# DC075B_LMK_CLOCK_CIRCUIT.net
KiCad netlist of a schematic drawn in Altium Designer
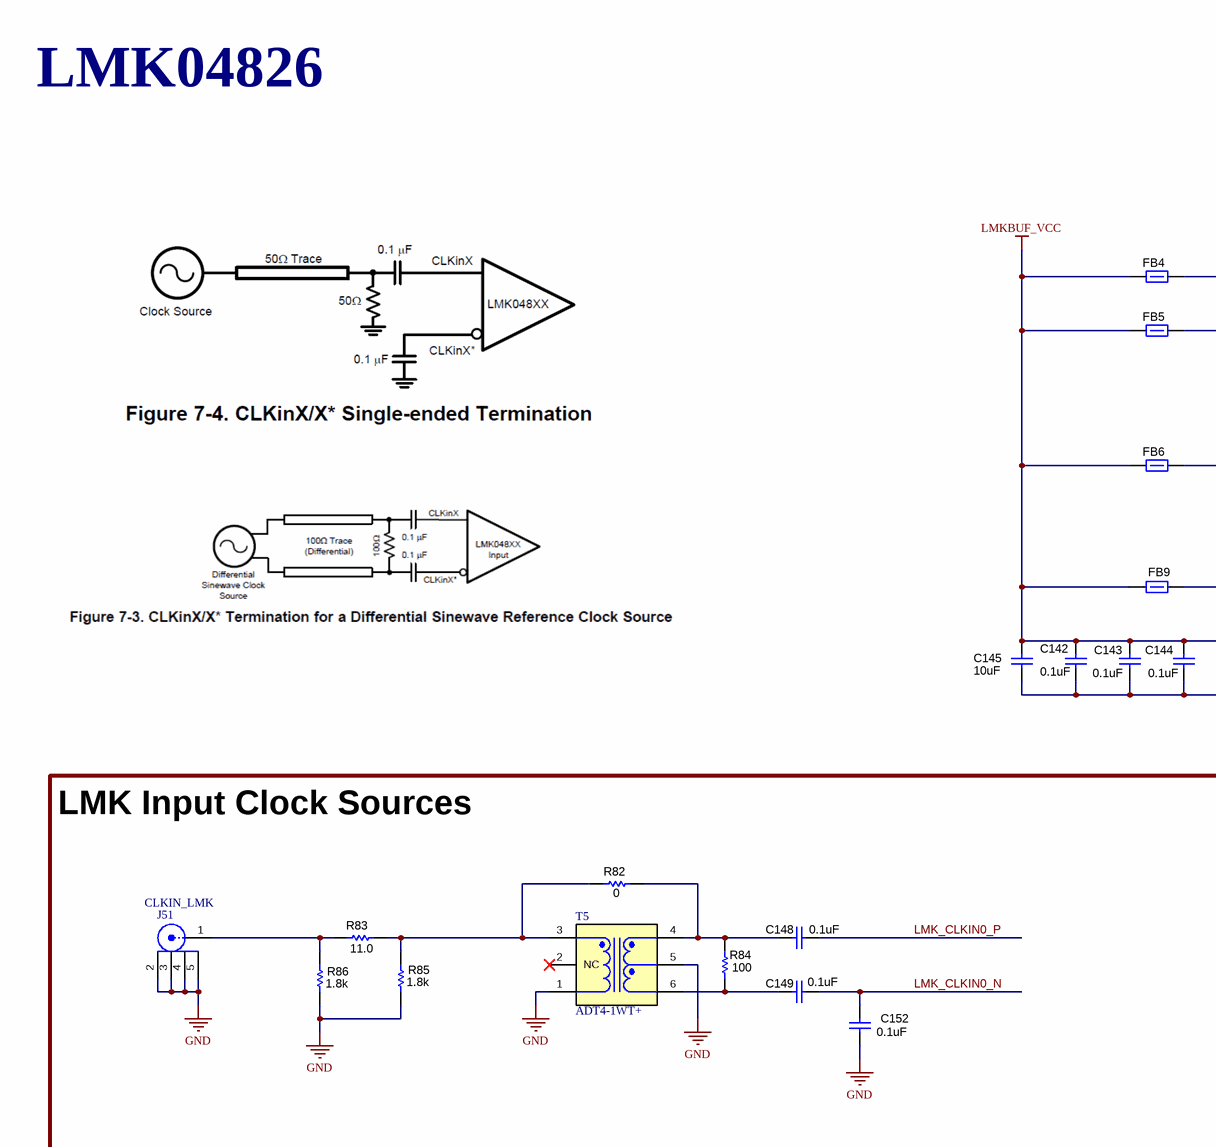
[diagram p0: DC075B_LMK_CLOCK_CIRCUIT.SchDoc, top left]
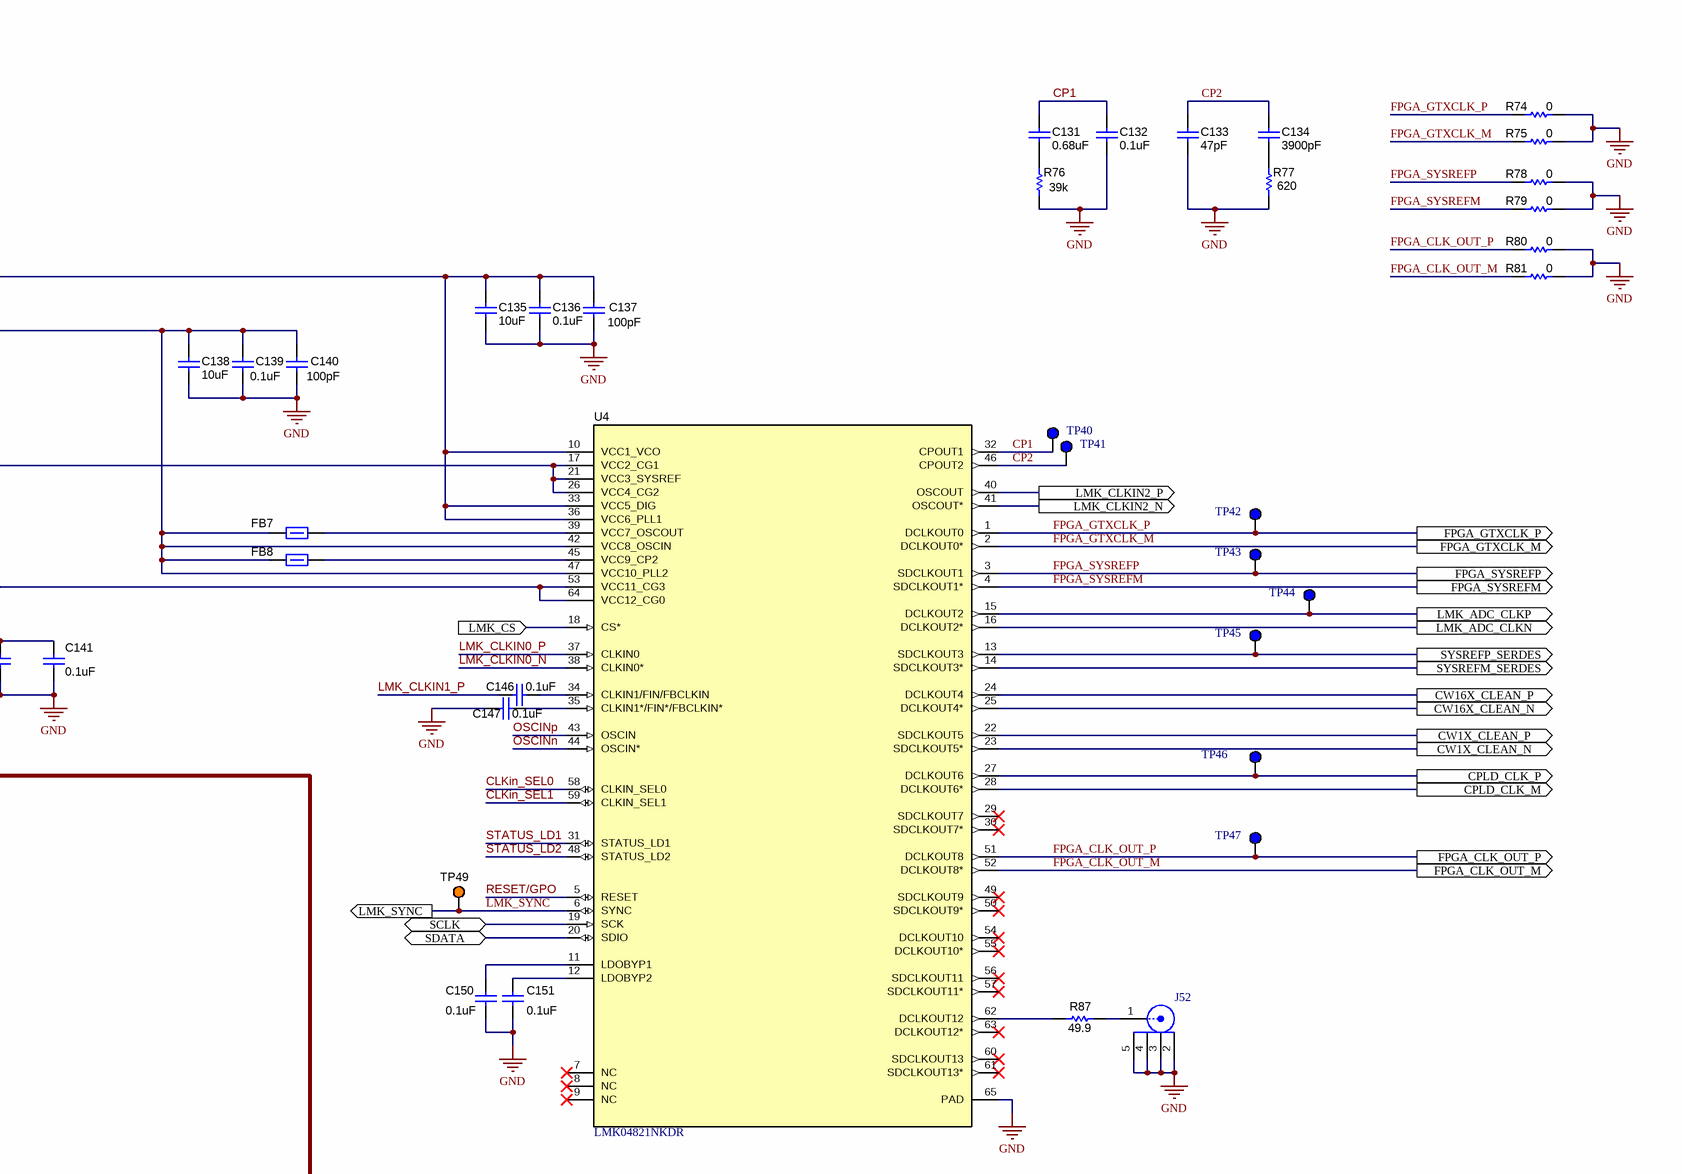
[diagram p1: DC075B_LMK_CLOCK_CIRCUIT.SchDoc, top right]
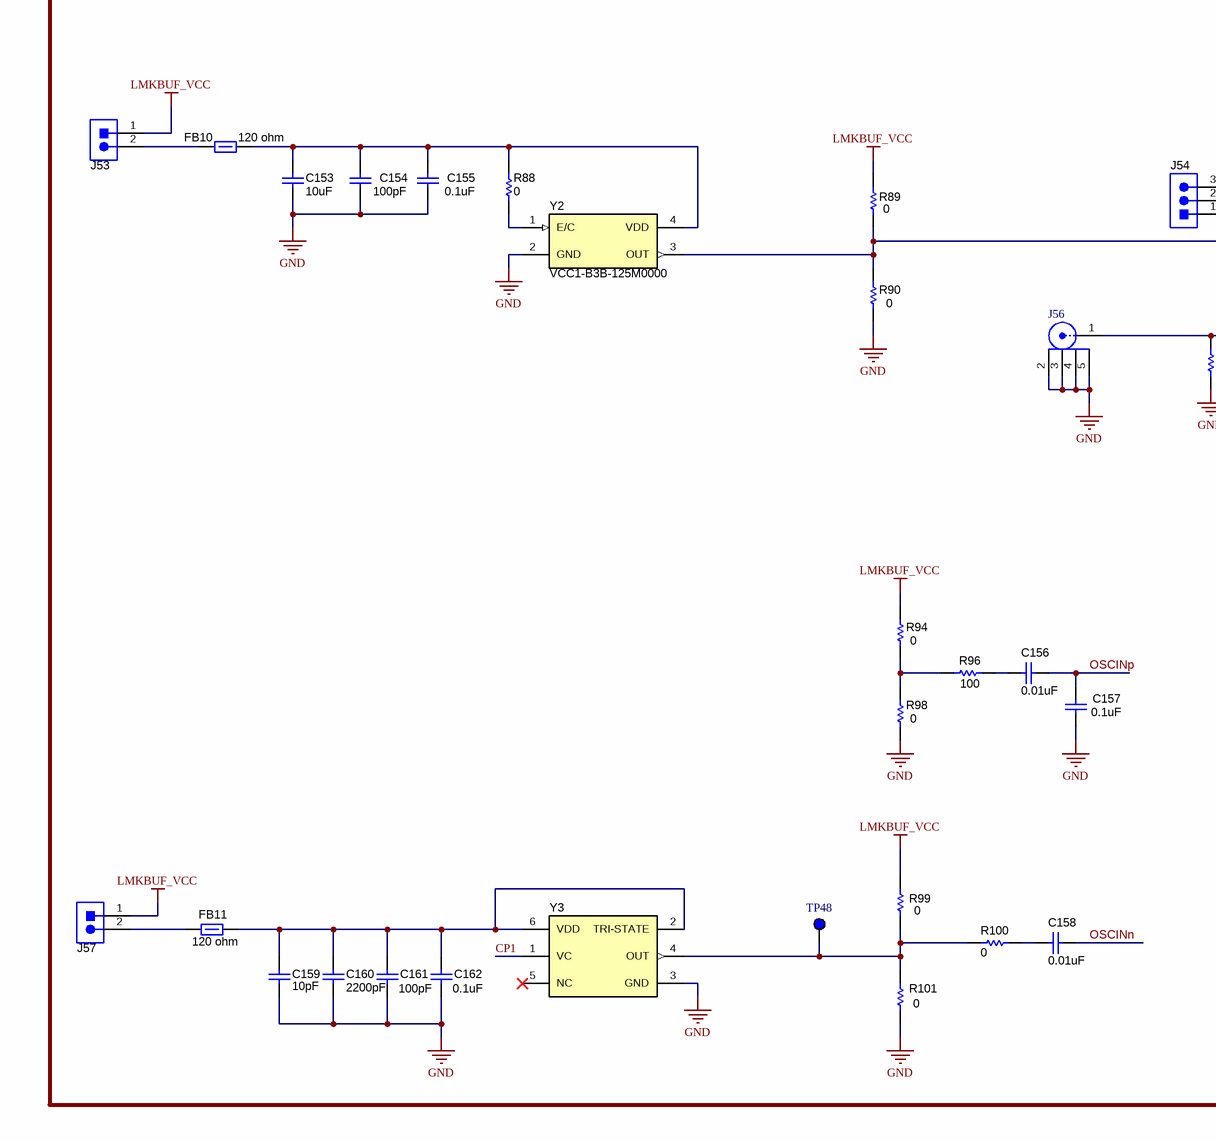
[diagram p2: DC075B_LMK_CLOCK_CIRCUIT.SchDoc, bottom left]
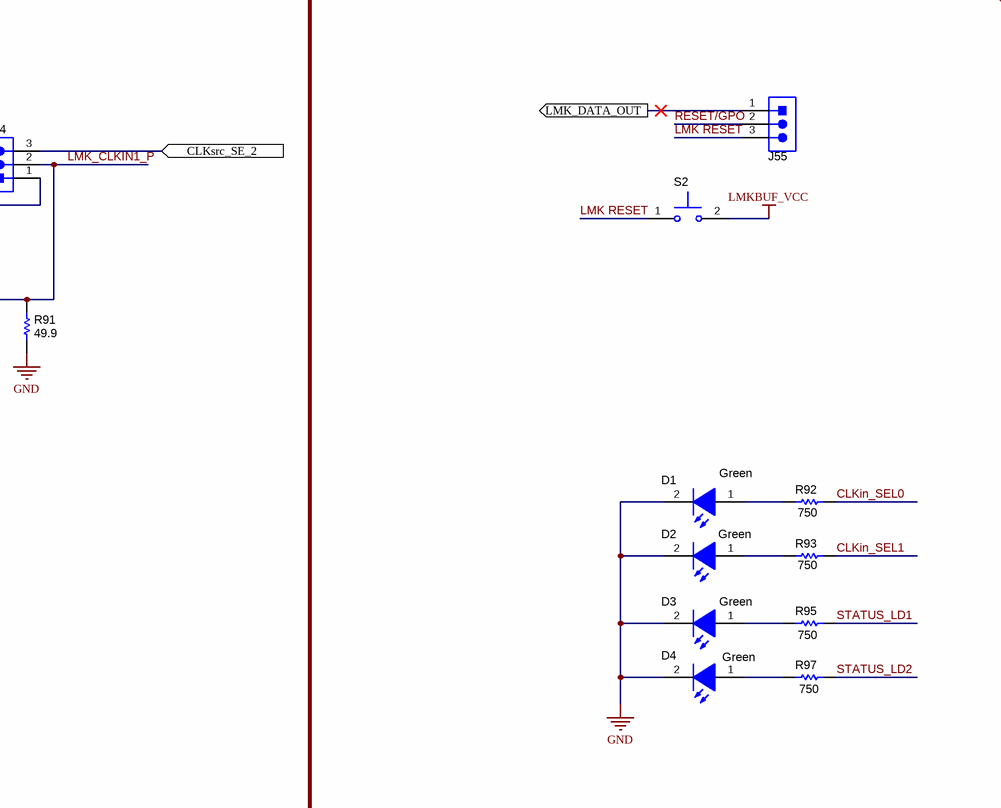
[diagram p3: DC075B_LMK_CLOCK_CIRCUIT.SchDoc, bottom right]

(export (version "E")
  (design (tool "Eeschema 10.0.6"))
  (components
    (comp (ref "C131")
      (value "0.68uF")
      (footprint "0603_HV")
      (description "CAP, CERM, 0.68 uF, 10 V, +/- 10%, X5R, 0603")
      (fields
        (field (name "PARTNUMBER") "C0603C684K8PACTU")
        (field (name "MANUFACTURER") "Kemet")
        (field (name "PUBLISHER") "Texas Instruments")
      )
      (libsource (lib "Altium Vault - TI") (part "Capacitor"))
    )
    (comp (ref "C132")
      (value "0.1uF")
      (footprint "0402")
      (description "CAP, CERM, 0.1 uF, 16 V, +/- 10%, X7R, 0402")
      (fields
        (field (name "PARTNUMBER") "GRM155R71C104KA88D")
        (field (name "MANUFACTURER") "MuRata")
        (field (name "PUBLISHER") "Texas Instruments")
      )
      (libsource (lib "Altium Vault - TI") (part "Capacitor"))
    )
    (comp (ref "C133")
      (value "C0603C470J1GACAUTO")
      (footprint "0603")
      (description "CAP, CERM, 47 pF, 100 V,+/- 5%, C0G/NP0, AEC-Q200 Grade 1, 0603")
      (fields (field (name "VALUEDISPLAYED") "47pF") (field (name "MANUFACTURER") "Kemet"))
      (libsource (lib "Altium Vault - TI") (part "CMP-0085572-1"))
    )
    (comp (ref "C134")
      (value "3900pF")
      (footprint "0402")
      (description "CAP, CERM, 3900 pF, 50 V,+/- 10%, X7R, 0402")
      (fields
        (field (name "PARTNUMBER") "CL05B392KB5NNNC")
        (field (name "MANUFACTURER") "Samsung Electro-Mechanics")
      )
      (libsource (lib "Altium Vault - TI") (part "CMP-0085576-2"))
    )
    (comp (ref "C135")
      (value "10uF")
      (footprint "0603_HV")
      (description "CAP, CERM, 10 uF, 6.3 V, +/- 20%, X5R, 0603")
      (fields
        (field (name "PARTNUMBER") "GRM188R60J106ME47D")
        (field (name "MANUFACTURER") "MuRata")
        (field (name "PUBLISHER") "Texas Instruments")
      )
      (libsource (lib "Altium Vault - TI") (part "Capacitor"))
    )
    (comp (ref "C136")
      (value "0.1uF")
      (footprint "0402")
      (description "CAP, CERM, 0.1 uF, 16 V, +/- 10%, X7R, 0402")
      (fields
        (field (name "PARTNUMBER") "GRM155R71C104KA88D")
        (field (name "MANUFACTURER") "MuRata")
        (field (name "PUBLISHER") "Texas Instruments")
      )
      (libsource (lib "Altium Vault - TI") (part "Capacitor"))
    )
    (comp (ref "C137")
      (value "100pF")
      (footprint "0402")
      (description "CAP, CERM, 100 pF, 50 V, +/- 10%, X7R, 0402")
      (fields
        (field (name "PARTNUMBER") "CC0402KRX7R9BB101")
        (field (name "MANUFACTURER") "Yageo America")
        (field (name "PUBLISHER") "Texas Instruments")
      )
      (libsource (lib "Altium Vault - TI") (part "Capacitor"))
    )
    (comp (ref "C138")
      (value "10uF")
      (footprint "0603_HV")
      (description "CAP, CERM, 10 uF, 6.3 V, +/- 20%, X5R, 0603")
      (fields
        (field (name "PARTNUMBER") "GRM188R60J106ME47D")
        (field (name "MANUFACTURER") "MuRata")
        (field (name "PUBLISHER") "Texas Instruments")
      )
      (libsource (lib "Altium Vault - TI") (part "Capacitor"))
    )
    (comp (ref "C139")
      (value "0.1uF")
      (footprint "0402")
      (description "CAP, CERM, 0.1 uF, 16 V, +/- 10%, X7R, 0402")
      (fields
        (field (name "PARTNUMBER") "GRM155R71C104KA88D")
        (field (name "MANUFACTURER") "MuRata")
        (field (name "PUBLISHER") "Texas Instruments")
      )
      (libsource (lib "Altium Vault - TI") (part "Capacitor"))
    )
    (comp (ref "C140")
      (value "100pF")
      (footprint "0402")
      (description "CAP, CERM, 100 pF, 50 V, +/- 10%, X7R, 0402")
      (fields
        (field (name "PARTNUMBER") "CC0402KRX7R9BB101")
        (field (name "MANUFACTURER") "Yageo America")
        (field (name "PUBLISHER") "Texas Instruments")
      )
      (libsource (lib "Altium Vault - TI") (part "Capacitor"))
    )
    (comp (ref "C141")
      (value "0.1uF")
      (footprint "0402")
      (description "CAP, CERM, 0.1 uF, 16 V, +/- 10%, X7R, 0402")
      (fields
        (field (name "PARTNUMBER") "GRM155R71C104KA88D")
        (field (name "MANUFACTURER") "MuRata")
        (field (name "PUBLISHER") "Texas Instruments")
      )
      (libsource (lib "Altium Vault - TI") (part "Capacitor"))
    )
    (comp (ref "C142")
      (value "0.1uF")
      (footprint "0402")
      (description "CAP, CERM, 0.1 uF, 16 V, +/- 10%, X7R, 0402")
      (fields
        (field (name "PARTNUMBER") "GRM155R71C104KA88D")
        (field (name "MANUFACTURER") "MuRata")
        (field (name "PUBLISHER") "Texas Instruments")
      )
      (libsource (lib "Altium Vault - TI") (part "Capacitor"))
    )
    (comp (ref "C143")
      (value "0.1uF")
      (footprint "0402")
      (description "CAP, CERM, 0.1 uF, 16 V, +/- 10%, X7R, 0402")
      (fields
        (field (name "PARTNUMBER") "GRM155R71C104KA88D")
        (field (name "MANUFACTURER") "MuRata")
        (field (name "PUBLISHER") "Texas Instruments")
      )
      (libsource (lib "Altium Vault - TI") (part "Capacitor"))
    )
    (comp (ref "C144")
      (value "0.1uF")
      (footprint "0402")
      (description "CAP, CERM, 0.1 uF, 16 V, +/- 10%, X7R, 0402")
      (fields
        (field (name "PARTNUMBER") "GRM155R71C104KA88D")
        (field (name "MANUFACTURER") "MuRata")
        (field (name "PUBLISHER") "Texas Instruments")
      )
      (libsource (lib "Altium Vault - TI") (part "Capacitor"))
    )
    (comp (ref "C145")
      (value "10uF")
      (footprint "0603_HV")
      (description "CAP, CERM, 10 uF, 6.3 V, +/- 20%, X5R, 0603")
      (fields
        (field (name "PARTNUMBER") "GRM188R60J106ME47D")
        (field (name "MANUFACTURER") "MuRata")
        (field (name "PUBLISHER") "Texas Instruments")
      )
      (libsource (lib "Altium Vault - TI") (part "Capacitor"))
    )
    (comp (ref "C146")
      (value "0.1uF")
      (footprint "0402")
      (description "CAP, CERM, 0.1 uF, 16 V, +/- 10%, X7R, 0402")
      (fields
        (field (name "PARTNUMBER") "GRM155R71C104KA88D")
        (field (name "MANUFACTURER") "MuRata")
        (field (name "PUBLISHER") "Texas Instruments")
      )
      (libsource (lib "Altium Vault - TI") (part "Capacitor"))
    )
    (comp (ref "C147")
      (value "0.1uF")
      (footprint "0402")
      (description "CAP, CERM, 0.1 uF, 16 V, +/- 10%, X7R, 0402")
      (fields
        (field (name "PARTNUMBER") "GRM155R71C104KA88D")
        (field (name "MANUFACTURER") "MuRata")
        (field (name "PUBLISHER") "Texas Instruments")
      )
      (libsource (lib "Altium Vault - TI") (part "Capacitor"))
    )
    (comp (ref "C148")
      (value "0.1uF")
      (footprint "0402")
      (description "CAP, CERM, 0.1 uF, 16 V, +/- 10%, X7R, 0402")
      (fields
        (field (name "PARTNUMBER") "GRM155R71C104KA88D")
        (field (name "MANUFACTURER") "MuRata")
        (field (name "PUBLISHER") "Texas Instruments")
      )
      (libsource (lib "Altium Vault - TI") (part "Capacitor"))
    )
    (comp (ref "C149")
      (value "0.1uF")
      (footprint "0402")
      (description "CAP, CERM, 0.1 uF, 16 V, +/- 10%, X7R, 0402")
      (fields
        (field (name "PARTNUMBER") "GRM155R71C104KA88D")
        (field (name "MANUFACTURER") "MuRata")
        (field (name "PUBLISHER") "Texas Instruments")
      )
      (libsource (lib "Altium Vault - TI") (part "Capacitor"))
    )
    (comp (ref "C150")
      (value "0.1uF")
      (footprint "0402")
      (description "CAP, CERM, 0.1 uF, 16 V, +/- 10%, X7R, 0402")
      (fields
        (field (name "PARTNUMBER") "GRM155R71C104KA88D")
        (field (name "MANUFACTURER") "MuRata")
        (field (name "PUBLISHER") "Texas Instruments")
      )
      (libsource (lib "Altium Vault - TI") (part "Capacitor"))
    )
    (comp (ref "C151")
      (value "0.1uF")
      (footprint "0402")
      (description "CAP, CERM, 0.1 uF, 16 V, +/- 10%, X7R, 0402")
      (fields
        (field (name "PARTNUMBER") "GRM155R71C104KA88D")
        (field (name "MANUFACTURER") "MuRata")
        (field (name "PUBLISHER") "Texas Instruments")
      )
      (libsource (lib "Altium Vault - TI") (part "Capacitor"))
    )
    (comp (ref "C152")
      (value "0.1uF")
      (footprint "0603_HV")
      (description "CAP, CERM, 0.1 uF, 25 V, +/- 5%, X7R, 0603")
      (fields
        (field (name "PARTNUMBER") "06033C104JAT2A")
        (field (name "MANUFACTURER") "AVX")
        (field (name "PUBLISHER") "Texas Instruments")
      )
      (libsource (lib "Altium Vault - TI") (part "Capacitor"))
    )
    (comp (ref "C153")
      (value "10uF")
      (footprint "0603_HV")
      (description "CAP, CERM, 10 uF, 6.3 V, +/- 20%, X5R, 0603")
      (fields
        (field (name "PARTNUMBER") "GRM188R60J106ME47D")
        (field (name "MANUFACTURER") "MuRata")
        (field (name "PUBLISHER") "Texas Instruments")
      )
      (libsource (lib "Altium Vault - TI") (part "Capacitor"))
    )
    (comp (ref "C154")
      (value "100pF")
      (footprint "0402")
      (description "CAP, CERM, 100 pF, 50 V, +/- 10%, X7R, 0402")
      (fields
        (field (name "PARTNUMBER") "CC0402KRX7R9BB101")
        (field (name "MANUFACTURER") "Yageo America")
        (field (name "PUBLISHER") "Texas Instruments")
      )
      (libsource (lib "Altium Vault - TI") (part "Capacitor"))
    )
    (comp (ref "C155")
      (value "0.1uF")
      (footprint "0402")
      (description "CAP, CERM, 0.1 uF, 16 V, +/- 10%, X7R, 0402")
      (fields
        (field (name "PARTNUMBER") "GRM155R71C104KA88D")
        (field (name "MANUFACTURER") "MuRata")
        (field (name "PUBLISHER") "Texas Instruments")
      )
      (libsource (lib "Altium Vault - TI") (part "Capacitor"))
    )
    (comp (ref "C156")
      (value "GRM155R61C103KA01D")
      (footprint "0402")
      (description "CAP, CERM, 0.01 uF, 16 V, +/- 10%, X5R, 0402")
      (fields
        (field (name "VALUEDISPLAYED") "0.01uF")
        (field (name "MANUFACTURER") "MuRata")
        (field (name "PUBLISHER") "Texas Instruments")
      )
      (libsource (lib "Altium Vault - TI") (part "Capacitor"))
    )
    (comp (ref "C157")
      (value "0.1uF")
      (footprint "0402")
      (description "CAP, CERM, 0.1 uF, 16 V, +/- 10%, X7R, 0402")
      (fields
        (field (name "PARTNUMBER") "GRM155R71C104KA88D")
        (field (name "MANUFACTURER") "MuRata")
        (field (name "PUBLISHER") "Texas Instruments")
      )
      (libsource (lib "Altium Vault - TI") (part "Capacitor"))
    )
    (comp (ref "C158")
      (value "GRM155R61C103KA01D")
      (footprint "0402")
      (description "CAP, CERM, 0.01 uF, 16 V, +/- 10%, X5R, 0402")
      (fields
        (field (name "VALUEDISPLAYED") "0.01uF")
        (field (name "MANUFACTURER") "MuRata")
        (field (name "PUBLISHER") "Texas Instruments")
      )
      (libsource (lib "Altium Vault - TI") (part "Capacitor"))
    )
    (comp (ref "C159")
      (value "C0402C100C8GACTU")
      (footprint "0402")
      (description "CAP, CERM, 10 pF, 10 V,+/- 2.5%, C0G/NP0, 0402")
      (fields
        (field (name "MANUFACTURER") "Kemet")
        (field (name "VALUEDISPLAYED") "10pF")
        (field (name "PUBLISHER") "Texas Instruments")
      )
      (libsource (lib "Altium Vault - TI") (part "CMP-0064914-2"))
    )
    (comp (ref "C160")
      (value "500R07W222KV4T")
      (footprint "0402_065")
      (description "CAP, CERM, 2200 pF, 50 V,+/- 10%, X7R, 0402")
      (fields (field (name "VALUEDISPLAYED") "2200pF") (field (name "MANUFACTURER") "Johanson Technology"))
      (libsource (lib "Altium Vault - TI") (part "Capacitor"))
    )
    (comp (ref "C161")
      (value "100pF")
      (footprint "0402")
      (description "CAP, CERM, 100 pF, 50 V, +/- 10%, X7R, 0402")
      (fields
        (field (name "PARTNUMBER") "CC0402KRX7R9BB101")
        (field (name "MANUFACTURER") "Yageo America")
        (field (name "PUBLISHER") "Texas Instruments")
      )
      (libsource (lib "Altium Vault - TI") (part "Capacitor"))
    )
    (comp (ref "C162")
      (value "0.1uF")
      (footprint "0402")
      (description "CAP, CERM, 0.1 uF, 16 V, +/- 10%, X7R, 0402")
      (fields
        (field (name "PARTNUMBER") "GRM155R71C104KA88D")
        (field (name "MANUFACTURER") "MuRata")
        (field (name "PUBLISHER") "Texas Instruments")
      )
      (libsource (lib "Altium Vault - TI") (part "Capacitor"))
    )
    (comp (ref "D1")
      (value "Green")
      (footprint "LED_LTST-C190_G")
      (description "LED, Green, SMD")
      (fields (field (name "MANUFACTURER") "Lite-On") (field (name "PARTNUMBER") "LTST-C190KGKT"))
      (libsource (lib "Altium Vault - TI") (part "CMP-0002840-2"))
    )
    (comp (ref "D2")
      (value "Green")
      (footprint "LED_LTST-C190_G")
      (description "LED, Green, SMD")
      (fields (field (name "MANUFACTURER") "Lite-On") (field (name "PARTNUMBER") "LTST-C190KGKT"))
      (libsource (lib "Altium Vault - TI") (part "CMP-0002840-2"))
    )
    (comp (ref "D3")
      (value "Green")
      (footprint "LED_LTST-C190_G")
      (description "LED, Green, SMD")
      (fields (field (name "MANUFACTURER") "Lite-On") (field (name "PARTNUMBER") "LTST-C190KGKT"))
      (libsource (lib "Altium Vault - TI") (part "CMP-0002840-2"))
    )
    (comp (ref "D4")
      (value "Green")
      (footprint "LED_LTST-C190_G")
      (description "LED, Green, SMD")
      (fields (field (name "MANUFACTURER") "Lite-On") (field (name "PARTNUMBER") "LTST-C190KGKT"))
      (libsource (lib "Altium Vault - TI") (part "CMP-0002840-2"))
    )
    (comp (ref "FB4")
      (value "BLM21AG121SN1D")
      (footprint "0805")
      (description "Ferrite Bead, 120 ohm @ 100 MHz, 0.8 A, 0805")
      (fields (field (name "MANUFACTURER") "MuRata") (field (name "PUBLISHER") "Texas Instruments"))
      (libsource (lib "Altium Vault - TI") (part "Ferrite_Bead"))
    )
    (comp (ref "FB5")
      (value "BLM21AG121SN1D")
      (footprint "0805")
      (description "Ferrite Bead, 120 ohm @ 100 MHz, 0.8 A, 0805")
      (fields (field (name "MANUFACTURER") "MuRata") (field (name "PUBLISHER") "Texas Instruments"))
      (libsource (lib "Altium Vault - TI") (part "Ferrite_Bead"))
    )
    (comp (ref "FB6")
      (value "BLM21AG121SN1D")
      (footprint "0805")
      (description "Ferrite Bead, 120 ohm @ 100 MHz, 0.8 A, 0805")
      (fields (field (name "MANUFACTURER") "MuRata") (field (name "PUBLISHER") "Texas Instruments"))
      (libsource (lib "Altium Vault - TI") (part "Ferrite_Bead"))
    )
    (comp (ref "FB7")
      (value "BLM21AG121SN1D")
      (footprint "0805")
      (description "Ferrite Bead, 120 ohm @ 100 MHz, 0.8 A, 0805")
      (fields (field (name "MANUFACTURER") "MuRata") (field (name "PUBLISHER") "Texas Instruments"))
      (libsource (lib "Altium Vault - TI") (part "Ferrite_Bead"))
    )
    (comp (ref "FB8")
      (value "BLM21AG121SN1D")
      (footprint "0805")
      (description "Ferrite Bead, 120 ohm @ 100 MHz, 0.8 A, 0805")
      (fields (field (name "MANUFACTURER") "MuRata") (field (name "PUBLISHER") "Texas Instruments"))
      (libsource (lib "Altium Vault - TI") (part "Ferrite_Bead"))
    )
    (comp (ref "FB9")
      (value "BLM21AG121SN1D")
      (footprint "0805")
      (description "Ferrite Bead, 120 ohm @ 100 MHz, 0.8 A, 0805")
      (fields (field (name "MANUFACTURER") "MuRata") (field (name "PUBLISHER") "Texas Instruments"))
      (libsource (lib "Altium Vault - TI") (part "Ferrite_Bead"))
    )
    (comp (ref "FB10")
      (value "120 ohm")
      (footprint "1206")
      (description "Ferrite Bead, 120 ohm @ 100 MHz, 4 A, 1206")
      (fields
        (field (name "MANUFACTURER") "Laird-Signal Integrity Products")
        (field (name "PARTNUMBER") "HI1206P121R-10")
        (field (name "PUBLISHER") "Texas Instruments")
      )
      (libsource (lib "Altium Vault - TI") (part "Ferrite_Bead"))
    )
    (comp (ref "FB11")
      (value "120 ohm")
      (footprint "1206")
      (description "Ferrite Bead, 120 ohm @ 100 MHz, 4 A, 1206")
      (fields
        (field (name "MANUFACTURER") "Laird-Signal Integrity Products")
        (field (name "PARTNUMBER") "HI1206P121R-10")
        (field (name "PUBLISHER") "Texas Instruments")
      )
      (libsource (lib "Altium Vault - TI") (part "Ferrite_Bead"))
    )
    (comp (ref "J51")
      (value "5-1814832-1")
      (footprint "TE_5-1814832-1")
      (description "SMA Straight PCB Socket Die Cast, 50 Ohm, TH")
      (fields (field (name "MANUFACTURER") "TE Connectivity") (field (name "PUBLISHER") "Texas Instruments"))
      (libsource (lib "Altium Vault - TI") (part "SMA_Contact1_GND2345"))
    )
    (comp (ref "J52")
      (value "5-1814832-1")
      (footprint "TE_5-1814832-1")
      (description "SMA Straight PCB Socket Die Cast, 50 Ohm, TH")
      (fields (field (name "MANUFACTURER") "TE Connectivity") (field (name "PUBLISHER") "Texas Instruments"))
      (libsource (lib "Altium Vault - TI") (part "SMA_Contact1_GND2345"))
    )
    (comp (ref "J53")
      (value "TSW-102-07-G-S")
      (footprint "TSW-102-07-G-S")
      (description "Header, 100mil, 2x1, Gold, TH")
      (fields (field (name "MANUFACTURER") "Samtec"))
      (libsource (lib "Altium Vault - TI") (part "Header_2x1"))
    )
    (comp (ref "J54")
      (value "TSW-103-07-G-S")
      (footprint "TSW-103-07-G-S")
      (description "Header, 100mil, 3x1, Gold, TH")
      (fields (field (name "MANUFACTURER") "Samtec"))
      (libsource (lib "Altium Vault - TI") (part "Header_3x1"))
    )
    (comp (ref "J55")
      (value "TSW-103-07-G-S")
      (footprint "TSW-103-07-G-S")
      (description "Header, 100mil, 3x1, Gold, TH")
      (fields (field (name "MANUFACTURER") "Samtec"))
      (libsource (lib "") (part "Header_3x1_1"))
    )
    (comp (ref "J56")
      (value "5-1814832-1")
      (footprint "TE_5-1814832-1")
      (description "SMA Straight PCB Socket Die Cast, 50 Ohm, TH")
      (fields (field (name "MANUFACTURER") "TE Connectivity") (field (name "PUBLISHER") "Texas Instruments"))
      (libsource (lib "Altium Vault - TI") (part "SMA_Contact1_GND2345"))
    )
    (comp (ref "J57")
      (value "TSW-102-07-G-S")
      (footprint "TSW-102-07-G-S")
      (description "Header, 100mil, 2x1, Gold, TH")
      (fields (field (name "MANUFACTURER") "Samtec"))
      (libsource (lib "Altium Vault - TI") (part "Header_2x1"))
    )
    (comp (ref "R74")
      (value "0")
      (footprint "0402")
      (description "RES, 0, 5%, 0.063 W, AEC-Q200 Grade 0, 0402")
      (fields (field (name "MANUFACTURER") "Vishay-Dale") (field (name "PARTNUMBER") "CRCW04020000Z0ED"))
      (libsource (lib "Altium Vault - TI") (part "Resistor"))
    )
    (comp (ref "R75")
      (value "0")
      (footprint "0402")
      (description "RES, 0, 5%, 0.063 W, AEC-Q200 Grade 0, 0402")
      (fields (field (name "MANUFACTURER") "Vishay-Dale") (field (name "PARTNUMBER") "CRCW04020000Z0ED"))
      (libsource (lib "Altium Vault - TI") (part "Resistor"))
    )
    (comp (ref "R76")
      (value "39k")
      (footprint "0402")
      (description "RES, 39 k, 5%, 0.063 W, AEC-Q200 Grade 0, 0402")
      (fields (field (name "MANUFACTURER") "Vishay-Dale") (field (name "PARTNUMBER") "CRCW040239K0JNED"))
      (libsource (lib "Altium Vault - TI") (part "Resistor"))
    )
    (comp (ref "R77")
      (value "620")
      (footprint "0402")
      (description "RES, 620, 5%, 0.063 W, AEC-Q200 Grade 0, 0402")
      (fields (field (name "MANUFACTURER") "Vishay-Dale") (field (name "PARTNUMBER") "CRCW0402620RJNED"))
      (libsource (lib "Altium Vault - TI") (part "Resistor"))
    )
    (comp (ref "R78")
      (value "0")
      (footprint "0402")
      (description "RES, 0, 5%, 0.063 W, AEC-Q200 Grade 0, 0402")
      (fields (field (name "MANUFACTURER") "Vishay-Dale") (field (name "PARTNUMBER") "CRCW04020000Z0ED"))
      (libsource (lib "Altium Vault - TI") (part "Resistor"))
    )
    (comp (ref "R79")
      (value "0")
      (footprint "0402")
      (description "RES, 0, 5%, 0.063 W, AEC-Q200 Grade 0, 0402")
      (fields (field (name "MANUFACTURER") "Vishay-Dale") (field (name "PARTNUMBER") "CRCW04020000Z0ED"))
      (libsource (lib "Altium Vault - TI") (part "Resistor"))
    )
    (comp (ref "R80")
      (value "0")
      (footprint "0402")
      (description "RES, 0, 5%, 0.063 W, AEC-Q200 Grade 0, 0402")
      (fields (field (name "MANUFACTURER") "Vishay-Dale") (field (name "PARTNUMBER") "CRCW04020000Z0ED"))
      (libsource (lib "Altium Vault - TI") (part "Resistor"))
    )
    (comp (ref "R81")
      (value "0")
      (footprint "0402")
      (description "RES, 0, 5%, 0.063 W, AEC-Q200 Grade 0, 0402")
      (fields (field (name "MANUFACTURER") "Vishay-Dale") (field (name "PARTNUMBER") "CRCW04020000Z0ED"))
      (libsource (lib "Altium Vault - TI") (part "Resistor"))
    )
    (comp (ref "R82")
      (value "0")
      (footprint "0402")
      (description "RES, 0, 5%, 0.063 W, AEC-Q200 Grade 0, 0402")
      (fields (field (name "MANUFACTURER") "Vishay-Dale") (field (name "PARTNUMBER") "CRCW04020000Z0ED"))
      (libsource (lib "Altium Vault - TI") (part "Resistor"))
    )
    (comp (ref "R83")
      (value "11.0")
      (footprint "0402")
      (description "RES, 11.0, 1%, 0.063 W, AEC-Q200 Grade 0, 0402")
      (fields (field (name "MANUFACTURER") "Vishay-Dale") (field (name "PARTNUMBER") "CRCW040211R0FKED"))
      (libsource (lib "Altium Vault - TI") (part "Resistor"))
    )
    (comp (ref "R84")
      (value "ERJ-2RKF1000X")
      (footprint "0402")
      (description "RES, 100, 1%, 0.1 W, 0402")
      (fields
        (field (name "MANUFACTURER") "Panasonic")
        (field (name "VALUEDISPLAYED") "100")
        (field (name "PUBLISHER") "Texas Instruments")
      )
      (libsource (lib "Altium Vault - TI") (part "Resistor"))
    )
    (comp (ref "R85")
      (value "1.8k")
      (footprint "0402")
      (description "RES, 1.8 k, 5%, 0.063 W, AEC-Q200 Grade 0, 0402")
      (fields (field (name "MANUFACTURER") "Vishay-Dale") (field (name "PARTNUMBER") "CRCW04021K80JNED"))
      (libsource (lib "Altium Vault - TI") (part "Resistor"))
    )
    (comp (ref "R86")
      (value "1.8k")
      (footprint "0402")
      (description "RES, 1.8 k, 5%, 0.063 W, AEC-Q200 Grade 0, 0402")
      (fields (field (name "MANUFACTURER") "Vishay-Dale") (field (name "PARTNUMBER") "CRCW04021K80JNED"))
      (libsource (lib "Altium Vault - TI") (part "Resistor"))
    )
    (comp (ref "R87")
      (value "49.9")
      (footprint "0402")
      (description "RES, 49.9, 1%, 0.063 W, AEC-Q200 Grade 0, 0402")
      (fields (field (name "MANUFACTURER") "Vishay-Dale") (field (name "PARTNUMBER") "CRCW040249R9FKED"))
      (libsource (lib "Altium Vault - TI") (part "Resistor"))
    )
    (comp (ref "R88")
      (value "CRCW04020000Z0ED")
      (footprint "0402")
      (description "RES, 0, 5%, 0.063 W, AEC-Q200 Grade 0, 0402")
      (fields (field (name "VALUEDISPLAYED") "0") (field (name "MANUFACTURER") "Vishay-Dale"))
      (libsource (lib "Altium Vault - TI") (part "Resistor"))
    )
    (comp (ref "R89")
      (value "0")
      (footprint "0402")
      (description "RES, 0, 5%, 0.063 W, AEC-Q200 Grade 0, 0402")
      (fields (field (name "MANUFACTURER") "Vishay-Dale") (field (name "PARTNUMBER") "CRCW04020000Z0ED"))
      (libsource (lib "Altium Vault - TI") (part "Resistor"))
    )
    (comp (ref "R90")
      (value "0")
      (footprint "0402")
      (description "RES, 0, 5%, 0.063 W, AEC-Q200 Grade 0, 0402")
      (fields (field (name "MANUFACTURER") "Vishay-Dale") (field (name "PARTNUMBER") "CRCW04020000Z0ED"))
      (libsource (lib "Altium Vault - TI") (part "Resistor"))
    )
    (comp (ref "R91")
      (value "49.9")
      (footprint "0402")
      (description "RES, 49.9, 1%, 0.063 W, AEC-Q200 Grade 0, 0402")
      (fields (field (name "MANUFACTURER") "Vishay-Dale") (field (name "PARTNUMBER") "CRCW040249R9FKED"))
      (libsource (lib "Altium Vault - TI") (part "Resistor"))
    )
    (comp (ref "R92")
      (value "750")
      (footprint "0402")
      (description "RES, 750, 5%, 0.063 W, AEC-Q200 Grade 0, 0402")
      (fields (field (name "MANUFACTURER") "Vishay-Dale") (field (name "PARTNUMBER") "CRCW0402750RJNED"))
      (libsource (lib "Altium Vault - TI") (part "Resistor"))
    )
    (comp (ref "R93")
      (value "750")
      (footprint "0402")
      (description "RES, 750, 5%, 0.063 W, AEC-Q200 Grade 0, 0402")
      (fields (field (name "MANUFACTURER") "Vishay-Dale") (field (name "PARTNUMBER") "CRCW0402750RJNED"))
      (libsource (lib "Altium Vault - TI") (part "Resistor"))
    )
    (comp (ref "R94")
      (value "0")
      (footprint "0402")
      (description "RES, 0, 5%, 0.063 W, AEC-Q200 Grade 0, 0402")
      (fields (field (name "MANUFACTURER") "Vishay-Dale") (field (name "PARTNUMBER") "CRCW04020000Z0ED"))
      (libsource (lib "Altium Vault - TI") (part "Resistor"))
    )
    (comp (ref "R95")
      (value "750")
      (footprint "0402")
      (description "RES, 750, 5%, 0.063 W, AEC-Q200 Grade 0, 0402")
      (fields (field (name "MANUFACTURER") "Vishay-Dale") (field (name "PARTNUMBER") "CRCW0402750RJNED"))
      (libsource (lib "Altium Vault - TI") (part "Resistor"))
    )
    (comp (ref "R96")
      (value "ERJ-2RKF1000X")
      (footprint "0402")
      (description "RES, 100, 1%, 0.1 W, 0402")
      (fields
        (field (name "MANUFACTURER") "Panasonic")
        (field (name "VALUEDISPLAYED") "100")
        (field (name "PUBLISHER") "Texas Instruments")
      )
      (libsource (lib "Altium Vault - TI") (part "Resistor"))
    )
    (comp (ref "R97")
      (value "750")
      (footprint "0402")
      (description "RES, 750, 5%, 0.063 W, AEC-Q200 Grade 0, 0402")
      (fields (field (name "MANUFACTURER") "Vishay-Dale") (field (name "PARTNUMBER") "CRCW0402750RJNED"))
      (libsource (lib "Altium Vault - TI") (part "Resistor"))
    )
    (comp (ref "R98")
      (value "0")
      (footprint "0402")
      (description "RES, 0, 5%, 0.063 W, AEC-Q200 Grade 0, 0402")
      (fields (field (name "MANUFACTURER") "Vishay-Dale") (field (name "PARTNUMBER") "CRCW04020000Z0ED"))
      (libsource (lib "Altium Vault - TI") (part "Resistor"))
    )
    (comp (ref "R99")
      (value "0")
      (footprint "0402")
      (description "RES, 0, 5%, 0.063 W, AEC-Q200 Grade 0, 0402")
      (fields (field (name "MANUFACTURER") "Vishay-Dale") (field (name "PARTNUMBER") "CRCW04020000Z0ED"))
      (libsource (lib "Altium Vault - TI") (part "Resistor"))
    )
    (comp (ref "R100")
      (value "CRCW04020000Z0ED")
      (footprint "0402")
      (description "RES, 0, 5%, 0.063 W, AEC-Q200 Grade 0, 0402")
      (fields (field (name "MANUFACTURER") "Vishay-Dale") (field (name "VALUEDISPLAYED") "0"))
      (libsource (lib "Altium Vault - TI") (part "Resistor"))
    )
    (comp (ref "R101")
      (value "0")
      (footprint "0402")
      (description "RES, 0, 5%, 0.063 W, AEC-Q200 Grade 0, 0402")
      (fields (field (name "MANUFACTURER") "Vishay-Dale") (field (name "PARTNUMBER") "CRCW04020000Z0ED"))
      (libsource (lib "Altium Vault - TI") (part "Resistor"))
    )
    (comp (ref "S2")
      (value "SKRKAEE020")
      (footprint "SW_SKRKAE")
      (description "Switch, SPST-NO, 0.05 A, 12 VDC, SMT")
      (fields (field (name "MANUFACTURER") "Alps") (field (name "PUBLISHER") "Texas Instruments"))
      (libsource (lib "Altium Vault - TI") (part "Switch_PushButton"))
    )
    (comp (ref "T5")
      (value "ADT4-1WT+")
      (footprint "MNC_CD542")
      (description "RF Transformer, 50 ohm, 2 to 775 MHz, SMT")
      (fields (field (name "MANUFACTURER") "Minicircuits") (field (name "PUBLISHER") "Texas Instruments"))
      (libsource (lib "Altium Vault - TI") (part "MNC_ADT4-1WT+"))
    )
    (comp (ref "TP40")
      (value "5117")
      (footprint "Keystone5117")
      (description "Test Point, Miniature, Blue, TH")
      (fields (field (name "MANUFACTURER") "Keystone") (field (name "PUBLISHER") "Texas Instruments"))
      (libsource (lib "Altium Vault - TI") (part "5117"))
    )
    (comp (ref "TP41")
      (value "5117")
      (footprint "Keystone5117")
      (description "Test Point, Miniature, Blue, TH")
      (fields (field (name "MANUFACTURER") "Keystone") (field (name "PUBLISHER") "Texas Instruments"))
      (libsource (lib "Altium Vault - TI") (part "5117"))
    )
    (comp (ref "TP42")
      (value "5117")
      (footprint "Keystone5117")
      (description "Test Point, Miniature, Blue, TH")
      (fields (field (name "MANUFACTURER") "Keystone") (field (name "PUBLISHER") "Texas Instruments"))
      (libsource (lib "Altium Vault - TI") (part "5117"))
    )
    (comp (ref "TP43")
      (value "5117")
      (footprint "Keystone5117")
      (description "Test Point, Miniature, Blue, TH")
      (fields (field (name "MANUFACTURER") "Keystone") (field (name "PUBLISHER") "Texas Instruments"))
      (libsource (lib "Altium Vault - TI") (part "5117"))
    )
    (comp (ref "TP44")
      (value "5117")
      (footprint "Keystone5117")
      (description "Test Point, Miniature, Blue, TH")
      (fields (field (name "MANUFACTURER") "Keystone") (field (name "PUBLISHER") "Texas Instruments"))
      (libsource (lib "Altium Vault - TI") (part "5117"))
    )
    (comp (ref "TP45")
      (value "5117")
      (footprint "Keystone5117")
      (description "Test Point, Miniature, Blue, TH")
      (fields (field (name "MANUFACTURER") "Keystone") (field (name "PUBLISHER") "Texas Instruments"))
      (libsource (lib "Altium Vault - TI") (part "5117"))
    )
    (comp (ref "TP46")
      (value "5117")
      (footprint "Keystone5117")
      (description "Test Point, Miniature, Blue, TH")
      (fields (field (name "MANUFACTURER") "Keystone") (field (name "PUBLISHER") "Texas Instruments"))
      (libsource (lib "Altium Vault - TI") (part "5117"))
    )
    (comp (ref "TP47")
      (value "5117")
      (footprint "Keystone5117")
      (description "Test Point, Miniature, Blue, TH")
      (fields (field (name "MANUFACTURER") "Keystone") (field (name "PUBLISHER") "Texas Instruments"))
      (libsource (lib "Altium Vault - TI") (part "5117"))
    )
    (comp (ref "TP48")
      (value "5117")
      (footprint "Keystone5117")
      (description "Test Point, Miniature, Blue, TH")
      (fields (field (name "MANUFACTURER") "Keystone") (field (name "PUBLISHER") "Texas Instruments"))
      (libsource (lib "Altium Vault - TI") (part "5117"))
    )
    (comp (ref "TP49")
      (value "5003")
      (footprint "Keystone5003")
      (description "Test Point, Miniature, Orange, TH")
      (fields (field (name "MANUFACTURER") "Keystone") (field (name "PUBLISHER") "Texas Instruments"))
      (libsource (lib "Altium Vault - TI") (part "5003"))
    )
    (comp (ref "U4")
      (value "LMK04821NKDR")
      (footprint "NKD0064A")
      (description "Ultra Low Jitter Synthesizer and Jitter Cleaner with JESD204B Support, NKD0064A (WQFN-64)")
      (fields
        (field (name "ALTERNATE PARTNUMBER") "LMK04821NKDT")
        (field (name "MANUFACTURER") "Texas Instruments")
      )
      (libsource (lib "Altium Vault - TI") (part "LMK0482x"))
    )
    (comp (ref "Y2")
      (value "VCC1-B3B-125M0000")
      (footprint "Vectron_VCC1")
      (description "OSC, 3.3 V, 125 MHz, 15 pF, SMD")
      (fields (field (name "MANUFACTURER") "Microsemi"))
      (libsource (lib "Altium Vault - TI") (part "OSC_4P_EC"))
    )
    (comp (ref "Y3")
      (value "ASVV-40.000MHZ-N102-T")
      (footprint "ABRACON_ASVV")
      (description "OSC, 40 MHz, 3.3V, SMD")
      (fields (field (name "MANUFACTURER") "Abracon Corporation"))
      (libsource (lib "Altium Vault - TI") (part "OSC_ASVV"))
    )
  )
  (nets
    (net (code "1") (name "/CLKin_SEL0") (class "Default")
      (node (ref "R92") (pin "2") (pinfunction "2_2") (pintype "passive"))
      (node (ref "U4") (pin "58") (pinfunction "CLKIN_SEL0_58") (pintype "bidirectional"))
    )
    (net (code "2") (name "/CLKin_SEL1") (class "Default")
      (node (ref "R93") (pin "2") (pinfunction "2_2") (pintype "passive"))
      (node (ref "U4") (pin "59") (pinfunction "CLKIN_SEL1_59") (pintype "bidirectional"))
    )
    (net (code "3") (name "/CLKsrc_SE_2") (class "Default")
      (node (ref "J54") (pin "3") (pinfunction "3_3") (pintype "passive"))
    )
    (net (code "4") (name "/CP1") (class "Default")
      (node (ref "C131") (pin "2") (pinfunction "2_2") (pintype "passive"))
      (node (ref "C132") (pin "2") (pinfunction "2_2") (pintype "passive"))
      (node (ref "TP40") (pin "1") (pintype "passive"))
      (node (ref "U4") (pin "32") (pinfunction "CPOUT1_32") (pintype "output"))
      (node (ref "Y3") (pin "1") (pinfunction "VC_1") (pintype "power_in"))
    )
    (net (code "5") (name "/CP2") (class "Default")
      (node (ref "C133") (pin "2") (pinfunction "2_2") (pintype "passive"))
      (node (ref "C134") (pin "2") (pinfunction "2_2") (pintype "passive"))
      (node (ref "TP41") (pin "1") (pintype "passive"))
      (node (ref "U4") (pin "46") (pinfunction "CPOUT2_46") (pintype "output"))
    )
    (net (code "6") (name "/CPLD_CLK_M") (class "Default")
      (node (ref "U4") (pin "28") (pinfunction "DCLKOUT6*_28") (pintype "output"))
    )
    (net (code "7") (name "/CPLD_CLK_P") (class "Default")
      (node (ref "TP46") (pin "1") (pintype "passive"))
      (node (ref "U4") (pin "27") (pinfunction "DCLKOUT6_27") (pintype "output"))
    )
    (net (code "8") (name "/CW1X_CLEAN_N") (class "Default")
      (node (ref "U4") (pin "23") (pinfunction "SDCLKOUT5*_23") (pintype "output"))
    )
    (net (code "9") (name "/CW1X_CLEAN_P") (class "Default")
      (node (ref "U4") (pin "22") (pinfunction "SDCLKOUT5_22") (pintype "output"))
    )
    (net (code "10") (name "/CW16X_CLEAN_N") (class "Default")
      (node (ref "U4") (pin "25") (pinfunction "DCLKOUT4*_25") (pintype "output"))
    )
    (net (code "11") (name "/CW16X_CLEAN_P") (class "Default")
      (node (ref "U4") (pin "24") (pinfunction "DCLKOUT4_24") (pintype "output"))
    )
    (net (code "12") (name "/FPGA_CLK_OUT_M") (class "Default")
      (node (ref "R81") (pin "2") (pinfunction "2_2") (pintype "passive"))
      (node (ref "U4") (pin "52") (pinfunction "DCLKOUT8*_52") (pintype "output"))
    )
    (net (code "13") (name "/FPGA_CLK_OUT_P") (class "Default")
      (node (ref "R80") (pin "1") (pinfunction "1_1") (pintype "passive"))
      (node (ref "TP47") (pin "1") (pintype "passive"))
      (node (ref "U4") (pin "51") (pinfunction "DCLKOUT8_51") (pintype "output"))
    )
    (net (code "14") (name "/FPGA_GTXCLK_M") (class "Default")
      (node (ref "R75") (pin "2") (pinfunction "2_2") (pintype "passive"))
      (node (ref "U4") (pin "2") (pinfunction "DCLKOUT0*_2") (pintype "output"))
    )
    (net (code "15") (name "/FPGA_GTXCLK_P") (class "Default")
      (node (ref "R74") (pin "1") (pinfunction "1_1") (pintype "passive"))
      (node (ref "TP42") (pin "1") (pintype "passive"))
      (node (ref "U4") (pin "1") (pinfunction "DCLKOUT0_1") (pintype "output"))
    )
    (net (code "16") (name "/FPGA_SYSREFM") (class "Default")
      (node (ref "R79") (pin "2") (pinfunction "2_2") (pintype "passive"))
      (node (ref "U4") (pin "4") (pinfunction "SDCLKOUT1*_4") (pintype "output"))
    )
    (net (code "17") (name "/FPGA_SYSREFP") (class "Default")
      (node (ref "R78") (pin "1") (pinfunction "1_1") (pintype "passive"))
      (node (ref "TP43") (pin "1") (pintype "passive"))
      (node (ref "U4") (pin "3") (pinfunction "SDCLKOUT1_3") (pintype "output"))
    )
    (net (code "18") (name "/LMK RESET") (class "Default")
      (node (ref "J55") (pin "3") (pinfunction "3_3") (pintype "passive"))
      (node (ref "S2") (pin "1") (pinfunction "1_1") (pintype "passive"))
    )
    (net (code "19") (name "/LMK_ADC_CLKN") (class "Default")
      (node (ref "U4") (pin "16") (pinfunction "DCLKOUT2*_16") (pintype "output"))
    )
    (net (code "20") (name "/LMK_ADC_CLKP") (class "Default")
      (node (ref "TP44") (pin "1") (pintype "passive"))
      (node (ref "U4") (pin "15") (pinfunction "DCLKOUT2_15") (pintype "output"))
    )
    (net (code "21") (name "/LMK_CLKIN0_N") (class "Default")
      (node (ref "C149") (pin "2") (pinfunction "2_2") (pintype "passive"))
      (node (ref "C152") (pin "1") (pinfunction "1_1") (pintype "passive"))
      (node (ref "U4") (pin "38") (pinfunction "CLKIN0*_38") (pintype "input"))
    )
    (net (code "22") (name "/LMK_CLKIN0_P") (class "Default")
      (node (ref "C148") (pin "2") (pinfunction "2_2") (pintype "passive"))
      (node (ref "U4") (pin "37") (pinfunction "CLKIN0_37") (pintype "input"))
    )
    (net (code "23") (name "/LMK_CLKIN1_P") (class "Default")
      (node (ref "C146") (pin "2") (pinfunction "2_2") (pintype "passive"))
      (node (ref "J54") (pin "2") (pinfunction "2_2") (pintype "passive"))
      (node (ref "J56") (pin "1") (pinfunction "1_1") (pintype "passive"))
      (node (ref "R91") (pin "1") (pinfunction "1_1") (pintype "passive"))
    )
    (net (code "24") (name "/LMK_CLKIN2_N") (class "Default")
      (node (ref "U4") (pin "41") (pinfunction "OSCOUT*_41") (pintype "output"))
    )
    (net (code "25") (name "/LMK_CLKIN2_P") (class "Default")
      (node (ref "U4") (pin "40") (pinfunction "OSCOUT_40") (pintype "output"))
    )
    (net (code "26") (name "/LMK_CS") (class "Default")
      (node (ref "U4") (pin "18") (pinfunction "CS*_18") (pintype "input"))
    )
    (net (code "27") (name "/LMK_DATA_OUT") (class "Default")
      (node (ref "J55") (pin "1") (pinfunction "1_1") (pintype "passive"))
    )
    (net (code "28") (name "/LMK_SYNC") (class "Default")
      (node (ref "TP49") (pin "1") (pintype "passive"))
      (node (ref "U4") (pin "6") (pinfunction "SYNC_6") (pintype "bidirectional"))
    )
    (net (code "29") (name "/OSCINn") (class "Default")
      (node (ref "C158") (pin "1") (pinfunction "1_1") (pintype "passive"))
      (node (ref "U4") (pin "44") (pinfunction "OSCIN*_44") (pintype "input"))
    )
    (net (code "30") (name "/OSCINp") (class "Default")
      (node (ref "C156") (pin "1") (pinfunction "1_1") (pintype "passive"))
      (node (ref "C157") (pin "1") (pinfunction "1_1") (pintype "passive"))
      (node (ref "U4") (pin "43") (pinfunction "OSCIN_43") (pintype "input"))
    )
    (net (code "31") (name "/RESET{slash}GPO") (class "Default")
      (node (ref "J55") (pin "2") (pinfunction "2_2") (pintype "passive"))
      (node (ref "U4") (pin "5") (pinfunction "RESET_5") (pintype "bidirectional"))
    )
    (net (code "32") (name "/SCLK") (class "Default")
      (node (ref "U4") (pin "19") (pinfunction "SCK_19") (pintype "input"))
    )
    (net (code "33") (name "/SDATA") (class "Default")
      (node (ref "U4") (pin "20") (pinfunction "SDIO_20") (pintype "bidirectional"))
    )
    (net (code "34") (name "/STATUS_LD1") (class "Default")
      (node (ref "R95") (pin "2") (pinfunction "2_2") (pintype "passive"))
      (node (ref "U4") (pin "31") (pinfunction "STATUS_LD1_31") (pintype "bidirectional"))
    )
    (net (code "35") (name "/STATUS_LD2") (class "Default")
      (node (ref "R97") (pin "2") (pinfunction "2_2") (pintype "passive"))
      (node (ref "U4") (pin "48") (pinfunction "STATUS_LD2_48") (pintype "bidirectional"))
    )
    (net (code "36") (name "/SYSREFM_SERDES") (class "Default")
      (node (ref "U4") (pin "14") (pinfunction "SDCLKOUT3*_14") (pintype "output"))
    )
    (net (code "37") (name "/SYSREFP_SERDES") (class "Default")
      (node (ref "TP45") (pin "1") (pintype "passive"))
      (node (ref "U4") (pin "13") (pinfunction "SDCLKOUT3_13") (pintype "output"))
    )
    (net (code "38") (name "GND") (class "Default")
      (node (ref "C132") (pin "1") (pinfunction "1_1") (pintype "passive"))
      (node (ref "C133") (pin "1") (pinfunction "1_1") (pintype "passive"))
      (node (ref "C135") (pin "1") (pinfunction "1_1") (pintype "passive"))
      (node (ref "C136") (pin "1") (pinfunction "1_1") (pintype "passive"))
      (node (ref "C137") (pin "1") (pinfunction "1_1") (pintype "passive"))
      (node (ref "C138") (pin "1") (pinfunction "1_1") (pintype "passive"))
      (node (ref "C139") (pin "1") (pinfunction "1_1") (pintype "passive"))
      (node (ref "C140") (pin "1") (pinfunction "1_1") (pintype "passive"))
      (node (ref "C141") (pin "1") (pinfunction "1_1") (pintype "passive"))
      (node (ref "C142") (pin "1") (pinfunction "1_1") (pintype "passive"))
      (node (ref "C143") (pin "1") (pinfunction "1_1") (pintype "passive"))
      (node (ref "C144") (pin "1") (pinfunction "1_1") (pintype "passive"))
      (node (ref "C145") (pin "1") (pinfunction "1_1") (pintype "passive"))
      (node (ref "C147") (pin "2") (pinfunction "2_2") (pintype "passive"))
      (node (ref "C150") (pin "2") (pinfunction "2_2") (pintype "passive"))
      (node (ref "C151") (pin "2") (pinfunction "2_2") (pintype "passive"))
      (node (ref "C152") (pin "2") (pinfunction "2_2") (pintype "passive"))
      (node (ref "C153") (pin "2") (pinfunction "2_2") (pintype "passive"))
      (node (ref "C154") (pin "2") (pinfunction "2_2") (pintype "passive"))
      (node (ref "C155") (pin "2") (pinfunction "2_2") (pintype "passive"))
      (node (ref "C157") (pin "2") (pinfunction "2_2") (pintype "passive"))
      (node (ref "C159") (pin "2") (pinfunction "2_2") (pintype "passive"))
      (node (ref "C160") (pin "2") (pinfunction "2_2") (pintype "passive"))
      (node (ref "C161") (pin "2") (pinfunction "2_2") (pintype "passive"))
      (node (ref "C162") (pin "2") (pinfunction "2_2") (pintype "passive"))
      (node (ref "D1") (pin "2") (pinfunction "K_2") (pintype "passive"))
      (node (ref "D2") (pin "2") (pinfunction "K_2") (pintype "passive"))
      (node (ref "D3") (pin "2") (pinfunction "K_2") (pintype "passive"))
      (node (ref "D4") (pin "2") (pinfunction "K_2") (pintype "passive"))
      (node (ref "J51") (pin "2") (pinfunction "2_2") (pintype "passive"))
      (node (ref "J51") (pin "3") (pinfunction "3_3") (pintype "passive"))
      (node (ref "J51") (pin "4") (pinfunction "4_4") (pintype "passive"))
      (node (ref "J51") (pin "5") (pinfunction "5_5") (pintype "passive"))
      (node (ref "J52") (pin "2") (pinfunction "2_2") (pintype "passive"))
      (node (ref "J52") (pin "3") (pinfunction "3_3") (pintype "passive"))
      (node (ref "J52") (pin "4") (pinfunction "4_4") (pintype "passive"))
      (node (ref "J52") (pin "5") (pinfunction "5_5") (pintype "passive"))
      (node (ref "J56") (pin "2") (pinfunction "2_2") (pintype "passive"))
      (node (ref "J56") (pin "3") (pinfunction "3_3") (pintype "passive"))
      (node (ref "J56") (pin "4") (pinfunction "4_4") (pintype "passive"))
      (node (ref "J56") (pin "5") (pinfunction "5_5") (pintype "passive"))
      (node (ref "R101") (pin "2") (pinfunction "2_2") (pintype "passive"))
      (node (ref "R74") (pin "2") (pinfunction "2_2") (pintype "passive"))
      (node (ref "R75") (pin "1") (pinfunction "1_1") (pintype "passive"))
      (node (ref "R76") (pin "1") (pinfunction "1_1") (pintype "passive"))
      (node (ref "R77") (pin "1") (pinfunction "1_1") (pintype "passive"))
      (node (ref "R78") (pin "2") (pinfunction "2_2") (pintype "passive"))
      (node (ref "R79") (pin "1") (pinfunction "1_1") (pintype "passive"))
      (node (ref "R80") (pin "2") (pinfunction "2_2") (pintype "passive"))
      (node (ref "R81") (pin "1") (pinfunction "1_1") (pintype "passive"))
      (node (ref "R85") (pin "2") (pinfunction "2_2") (pintype "passive"))
      (node (ref "R86") (pin "2") (pinfunction "2_2") (pintype "passive"))
      (node (ref "R90") (pin "2") (pinfunction "2_2") (pintype "passive"))
      (node (ref "R91") (pin "2") (pinfunction "2_2") (pintype "passive"))
      (node (ref "R98") (pin "2") (pinfunction "2_2") (pintype "passive"))
      (node (ref "T5") (pin "1") (pinfunction "1_1") (pintype "power_in"))
      (node (ref "T5") (pin "5") (pinfunction "5_5") (pintype "power_in"))
      (node (ref "U4") (pin "65") (pinfunction "PAD_65") (pintype "power_in"))
      (node (ref "Y2") (pin "2") (pinfunction "GND_2") (pintype "power_in"))
      (node (ref "Y3") (pin "3") (pinfunction "GND_3") (pintype "power_in"))
    )
    (net (code "39") (name "LMKBUF_VCC") (class "Default")
      (node (ref "C141") (pin "2") (pinfunction "2_2") (pintype "passive"))
      (node (ref "C142") (pin "2") (pinfunction "2_2") (pintype "passive"))
      (node (ref "C143") (pin "2") (pinfunction "2_2") (pintype "passive"))
      (node (ref "C144") (pin "2") (pinfunction "2_2") (pintype "passive"))
      (node (ref "C145") (pin "2") (pinfunction "2_2") (pintype "passive"))
      (node (ref "FB4") (pin "1") (pinfunction "1_1") (pintype "passive"))
      (node (ref "FB5") (pin "1") (pinfunction "1_1") (pintype "passive"))
      (node (ref "FB6") (pin "1") (pinfunction "1_1") (pintype "passive"))
      (node (ref "FB9") (pin "1") (pinfunction "1_1") (pintype "passive"))
      (node (ref "J53") (pin "1") (pinfunction "1_1") (pintype "passive"))
      (node (ref "J57") (pin "1") (pinfunction "1_1") (pintype "passive"))
      (node (ref "R89") (pin "1") (pinfunction "1_1") (pintype "passive"))
      (node (ref "R94") (pin "1") (pinfunction "1_1") (pintype "passive"))
      (node (ref "R99") (pin "1") (pinfunction "1_1") (pintype "passive"))
      (node (ref "S2") (pin "2") (pinfunction "2_2") (pintype "passive"))
    )
    (net (code "40") (name "Net-(C131-Pad1)") (class "Default")
      (node (ref "C131") (pin "1") (pinfunction "1_1") (pintype "passive"))
      (node (ref "R76") (pin "2") (pinfunction "2_2") (pintype "passive"))
    )
    (net (code "41") (name "Net-(C134-Pad1)") (class "Default")
      (node (ref "C134") (pin "1") (pinfunction "1_1") (pintype "passive"))
      (node (ref "R77") (pin "2") (pinfunction "2_2") (pintype "passive"))
    )
    (net (code "42") (name "Net-(C148-Pad1)") (class "Default")
      (node (ref "C148") (pin "1") (pinfunction "1_1") (pintype "passive"))
      (node (ref "R82") (pin "2") (pinfunction "2_2") (pintype "passive"))
      (node (ref "R84") (pin "2") (pinfunction "2_2") (pintype "passive"))
      (node (ref "T5") (pin "4") (pinfunction "4_4") (pintype "power_in"))
    )
    (net (code "43") (name "Net-(C149-Pad1)") (class "Default")
      (node (ref "C149") (pin "1") (pinfunction "1_1") (pintype "passive"))
      (node (ref "R84") (pin "1") (pinfunction "1_1") (pintype "passive"))
      (node (ref "T5") (pin "6") (pinfunction "6_6") (pintype "power_in"))
    )
    (net (code "44") (name "Net-(C156-Pad2)") (class "Default")
      (node (ref "C156") (pin "2") (pinfunction "2_2") (pintype "passive"))
      (node (ref "R96") (pin "1") (pinfunction "1_1") (pintype "passive"))
    )
    (net (code "45") (name "Net-(C158-Pad2)") (class "Default")
      (node (ref "C158") (pin "2") (pinfunction "2_2") (pintype "passive"))
      (node (ref "R100") (pin "1") (pinfunction "1_1") (pintype "passive"))
    )
    (net (code "46") (name "Net-(D1-A)") (class "Default")
      (node (ref "D1") (pin "1") (pinfunction "A_1") (pintype "passive"))
      (node (ref "R92") (pin "1") (pinfunction "1_1") (pintype "passive"))
    )
    (net (code "47") (name "Net-(D2-A)") (class "Default")
      (node (ref "D2") (pin "1") (pinfunction "A_1") (pintype "passive"))
      (node (ref "R93") (pin "1") (pinfunction "1_1") (pintype "passive"))
    )
    (net (code "48") (name "Net-(D3-A)") (class "Default")
      (node (ref "D3") (pin "1") (pinfunction "A_1") (pintype "passive"))
      (node (ref "R95") (pin "1") (pinfunction "1_1") (pintype "passive"))
    )
    (net (code "49") (name "Net-(D4-A)") (class "Default")
      (node (ref "D4") (pin "1") (pinfunction "A_1") (pintype "passive"))
      (node (ref "R97") (pin "1") (pinfunction "1_1") (pintype "passive"))
    )
    (net (code "50") (name "Net-(FB10-Pad1)") (class "Default")
      (node (ref "FB10") (pin "1") (pinfunction "1_1") (pintype "passive"))
      (node (ref "J53") (pin "2") (pinfunction "2_2") (pintype "passive"))
    )
    (net (code "51") (name "Net-(FB11-Pad1)") (class "Default")
      (node (ref "FB11") (pin "1") (pinfunction "1_1") (pintype "passive"))
      (node (ref "J57") (pin "2") (pinfunction "2_2") (pintype "passive"))
    )
    (net (code "52") (name "Net-(J51-Pad1)") (class "Default")
      (node (ref "J51") (pin "1") (pinfunction "1_1") (pintype "passive"))
      (node (ref "R83") (pin "1") (pinfunction "1_1") (pintype "passive"))
      (node (ref "R86") (pin "1") (pinfunction "1_1") (pintype "passive"))
    )
    (net (code "53") (name "Net-(J52-Pad1)") (class "Default")
      (node (ref "J52") (pin "1") (pinfunction "1_1") (pintype "passive"))
      (node (ref "R87") (pin "2") (pinfunction "2_2") (pintype "passive"))
    )
    (net (code "54") (name "Net-(R82-Pad1)") (class "Default")
      (node (ref "R82") (pin "1") (pinfunction "1_1") (pintype "passive"))
      (node (ref "R83") (pin "2") (pinfunction "2_2") (pintype "passive"))
      (node (ref "R85") (pin "1") (pinfunction "1_1") (pintype "passive"))
      (node (ref "T5") (pin "3") (pinfunction "3_3") (pintype "power_in"))
    )
    (net (code "55") (name "Net-(R94-Pad2)") (class "Default")
      (node (ref "R94") (pin "2") (pinfunction "2_2") (pintype "passive"))
      (node (ref "R96") (pin "2") (pinfunction "2_2") (pintype "passive"))
      (node (ref "R98") (pin "1") (pinfunction "1_1") (pintype "passive"))
    )
    (net (code "56") (name "Net-(U4-CLKIN1*{slash}FIN*{slash}FBCLKIN*)") (class "Default")
      (node (ref "C147") (pin "1") (pinfunction "1_1") (pintype "passive"))
      (node (ref "U4") (pin "35") (pinfunction "CLKIN1*/FIN*/FBCLKIN*_35") (pintype "input"))
    )
    (net (code "57") (name "Net-(U4-CLKIN1{slash}FIN{slash}FBCLKIN)") (class "Default")
      (node (ref "C146") (pin "1") (pinfunction "1_1") (pintype "passive"))
      (node (ref "U4") (pin "34") (pinfunction "CLKIN1/FIN/FBCLKIN_34") (pintype "input"))
    )
    (net (code "58") (name "Net-(U4-DCLKOUT12)") (class "Default")
      (node (ref "R87") (pin "1") (pinfunction "1_1") (pintype "passive"))
      (node (ref "U4") (pin "62") (pinfunction "DCLKOUT12_62") (pintype "output"))
    )
    (net (code "59") (name "Net-(U4-LDOBYP1)") (class "Default")
      (node (ref "C150") (pin "1") (pinfunction "1_1") (pintype "passive"))
      (node (ref "U4") (pin "11") (pinfunction "LDOBYP1_11") (pintype "passive"))
    )
    (net (code "60") (name "Net-(U4-LDOBYP2)") (class "Default")
      (node (ref "C151") (pin "1") (pinfunction "1_1") (pintype "passive"))
      (node (ref "U4") (pin "12") (pinfunction "LDOBYP2_12") (pintype "passive"))
    )
    (net (code "61") (name "Net-(U4-VCC1_VCO)") (class "Default")
      (node (ref "C135") (pin "2") (pinfunction "2_2") (pintype "passive"))
      (node (ref "C136") (pin "2") (pinfunction "2_2") (pintype "passive"))
      (node (ref "C137") (pin "2") (pinfunction "2_2") (pintype "passive"))
      (node (ref "FB4") (pin "2") (pinfunction "2_2") (pintype "passive"))
      (node (ref "U4") (pin "10") (pinfunction "VCC1_VCO_10") (pintype "passive"))
      (node (ref "U4") (pin "33") (pinfunction "VCC5_DIG_33") (pintype "power_in"))
      (node (ref "U4") (pin "36") (pinfunction "VCC6_PLL1_36") (pintype "power_in"))
    )
    (net (code "62") (name "Net-(U4-VCC2_CG1)") (class "Default")
      (node (ref "FB6") (pin "2") (pinfunction "2_2") (pintype "passive"))
      (node (ref "U4") (pin "17") (pinfunction "VCC2_CG1_17") (pintype "power_in"))
      (node (ref "U4") (pin "21") (pinfunction "VCC3_SYSREF_21") (pintype "power_in"))
      (node (ref "U4") (pin "26") (pinfunction "VCC4_CG2_26") (pintype "power_in"))
    )
    (net (code "63") (name "Net-(U4-VCC7_OSCOUT)") (class "Default")
      (node (ref "FB7") (pin "2") (pinfunction "2_2") (pintype "passive"))
      (node (ref "U4") (pin "39") (pinfunction "VCC7_OSCOUT_39") (pintype "passive"))
    )
    (net (code "64") (name "Net-(U4-VCC9_CP2)") (class "Default")
      (node (ref "FB8") (pin "2") (pinfunction "2_2") (pintype "passive"))
      (node (ref "U4") (pin "45") (pinfunction "VCC9_CP2_45") (pintype "power_in"))
    )
    (net (code "65") (name "Net-(U4-VCC10_PLL2)") (class "Default")
      (node (ref "C138") (pin "2") (pinfunction "2_2") (pintype "passive"))
      (node (ref "C139") (pin "2") (pinfunction "2_2") (pintype "passive"))
      (node (ref "C140") (pin "2") (pinfunction "2_2") (pintype "passive"))
      (node (ref "FB5") (pin "2") (pinfunction "2_2") (pintype "passive"))
      (node (ref "FB7") (pin "1") (pinfunction "1_1") (pintype "passive"))
      (node (ref "FB8") (pin "1") (pinfunction "1_1") (pintype "passive"))
      (node (ref "U4") (pin "42") (pinfunction "VCC8_OSCIN_42") (pintype "power_in"))
      (node (ref "U4") (pin "47") (pinfunction "VCC10_PLL2_47") (pintype "power_in"))
    )
    (net (code "66") (name "Net-(U4-VCC11_CG3)") (class "Default")
      (node (ref "FB9") (pin "2") (pinfunction "2_2") (pintype "passive"))
      (node (ref "U4") (pin "53") (pinfunction "VCC11_CG3_53") (pintype "power_in"))
      (node (ref "U4") (pin "64") (pinfunction "VCC12_CG0_64") (pintype "power_in"))
    )
    (net (code "67") (name "Net-(Y2-E{slash}C)") (class "Default")
      (node (ref "R88") (pin "2") (pinfunction "2_2") (pintype "passive"))
      (node (ref "Y2") (pin "1") (pinfunction "E/C_1") (pintype "input"))
    )
    (net (code "68") (name "Net-(Y2-OUT)") (class "Default")
      (node (ref "J54") (pin "1") (pinfunction "1_1") (pintype "passive"))
      (node (ref "R89") (pin "2") (pinfunction "2_2") (pintype "passive"))
      (node (ref "R90") (pin "1") (pinfunction "1_1") (pintype "passive"))
      (node (ref "Y2") (pin "3") (pinfunction "OUT_3") (pintype "output"))
    )
    (net (code "69") (name "Net-(Y2-VDD)") (class "Default")
      (node (ref "C153") (pin "1") (pinfunction "1_1") (pintype "passive"))
      (node (ref "C154") (pin "1") (pinfunction "1_1") (pintype "passive"))
      (node (ref "C155") (pin "1") (pinfunction "1_1") (pintype "passive"))
      (node (ref "FB10") (pin "2") (pinfunction "2_2") (pintype "passive"))
      (node (ref "R88") (pin "1") (pinfunction "1_1") (pintype "passive"))
      (node (ref "Y2") (pin "4") (pinfunction "VDD_4") (pintype "power_in"))
    )
    (net (code "70") (name "Net-(Y3-OUT)") (class "Default")
      (node (ref "R100") (pin "2") (pinfunction "2_2") (pintype "passive"))
      (node (ref "R101") (pin "1") (pinfunction "1_1") (pintype "passive"))
      (node (ref "R99") (pin "2") (pinfunction "2_2") (pintype "passive"))
      (node (ref "TP48") (pin "1") (pintype "passive"))
      (node (ref "Y3") (pin "4") (pinfunction "OUT_4") (pintype "output"))
    )
    (net (code "71") (name "Net-(Y3-TRI-STATE)") (class "Default")
      (node (ref "C159") (pin "1") (pinfunction "1_1") (pintype "passive"))
      (node (ref "C160") (pin "1") (pinfunction "1_1") (pintype "passive"))
      (node (ref "C161") (pin "1") (pinfunction "1_1") (pintype "passive"))
      (node (ref "C162") (pin "1") (pinfunction "1_1") (pintype "passive"))
      (node (ref "FB11") (pin "2") (pinfunction "2_2") (pintype "passive"))
      (node (ref "Y3") (pin "2") (pinfunction "TRI-STATE_2") (pintype "tri_state"))
      (node (ref "Y3") (pin "6") (pinfunction "VDD_6") (pintype "power_in"))
    )
    (net (code "72") (name "unconnected-(T5-NC-Pad2)") (class "Default")
      (node (ref "T5") (pin "2") (pinfunction "NC_2") (pintype "passive+no_connect"))
    )
    (net (code "73") (name "unconnected-(U4-DCLKOUT10*-Pad55)") (class "Default")
      (node (ref "U4") (pin "55") (pinfunction "DCLKOUT10*_55") (pintype "output+no_connect"))
    )
    (net (code "74") (name "unconnected-(U4-DCLKOUT10-Pad54)") (class "Default")
      (node (ref "U4") (pin "54") (pinfunction "DCLKOUT10_54") (pintype "output+no_connect"))
    )
    (net (code "75") (name "unconnected-(U4-DCLKOUT12*-Pad63)") (class "Default")
      (node (ref "U4") (pin "63") (pinfunction "DCLKOUT12*_63") (pintype "output+no_connect"))
    )
    (net (code "76") (name "unconnected-(U4-NC-Pad7)") (class "Default")
      (node (ref "U4") (pin "7") (pinfunction "NC_7") (pintype "passive+no_connect"))
    )
    (net (code "77") (name "unconnected-(U4-NC-Pad8)") (class "Default")
      (node (ref "U4") (pin "8") (pinfunction "NC_8") (pintype "passive+no_connect"))
    )
    (net (code "78") (name "unconnected-(U4-NC-Pad9)") (class "Default")
      (node (ref "U4") (pin "9") (pinfunction "NC_9") (pintype "passive+no_connect"))
    )
    (net (code "79") (name "unconnected-(U4-SDCLKOUT7*-Pad30)") (class "Default")
      (node (ref "U4") (pin "30") (pinfunction "SDCLKOUT7*_30") (pintype "output+no_connect"))
    )
    (net (code "80") (name "unconnected-(U4-SDCLKOUT7-Pad29)") (class "Default")
      (node (ref "U4") (pin "29") (pinfunction "SDCLKOUT7_29") (pintype "output+no_connect"))
    )
    (net (code "81") (name "unconnected-(U4-SDCLKOUT9*-Pad50)") (class "Default")
      (node (ref "U4") (pin "50") (pinfunction "SDCLKOUT9*_50") (pintype "output+no_connect"))
    )
    (net (code "82") (name "unconnected-(U4-SDCLKOUT9-Pad49)") (class "Default")
      (node (ref "U4") (pin "49") (pinfunction "SDCLKOUT9_49") (pintype "output+no_connect"))
    )
    (net (code "83") (name "unconnected-(U4-SDCLKOUT11*-Pad57)") (class "Default")
      (node (ref "U4") (pin "57") (pinfunction "SDCLKOUT11*_57") (pintype "output+no_connect"))
    )
    (net (code "84") (name "unconnected-(U4-SDCLKOUT11-Pad56)") (class "Default")
      (node (ref "U4") (pin "56") (pinfunction "SDCLKOUT11_56") (pintype "output+no_connect"))
    )
    (net (code "85") (name "unconnected-(U4-SDCLKOUT13*-Pad61)") (class "Default")
      (node (ref "U4") (pin "61") (pinfunction "SDCLKOUT13*_61") (pintype "output+no_connect"))
    )
    (net (code "86") (name "unconnected-(U4-SDCLKOUT13-Pad60)") (class "Default")
      (node (ref "U4") (pin "60") (pinfunction "SDCLKOUT13_60") (pintype "output+no_connect"))
    )
    (net (code "87") (name "unconnected-(Y3-NC-Pad5)") (class "Default")
      (node (ref "Y3") (pin "5") (pinfunction "NC_5") (pintype "passive+no_connect"))
    )
  )
)
